# TOP.net
KiCad netlist of a schematic drawn in Altium Designer
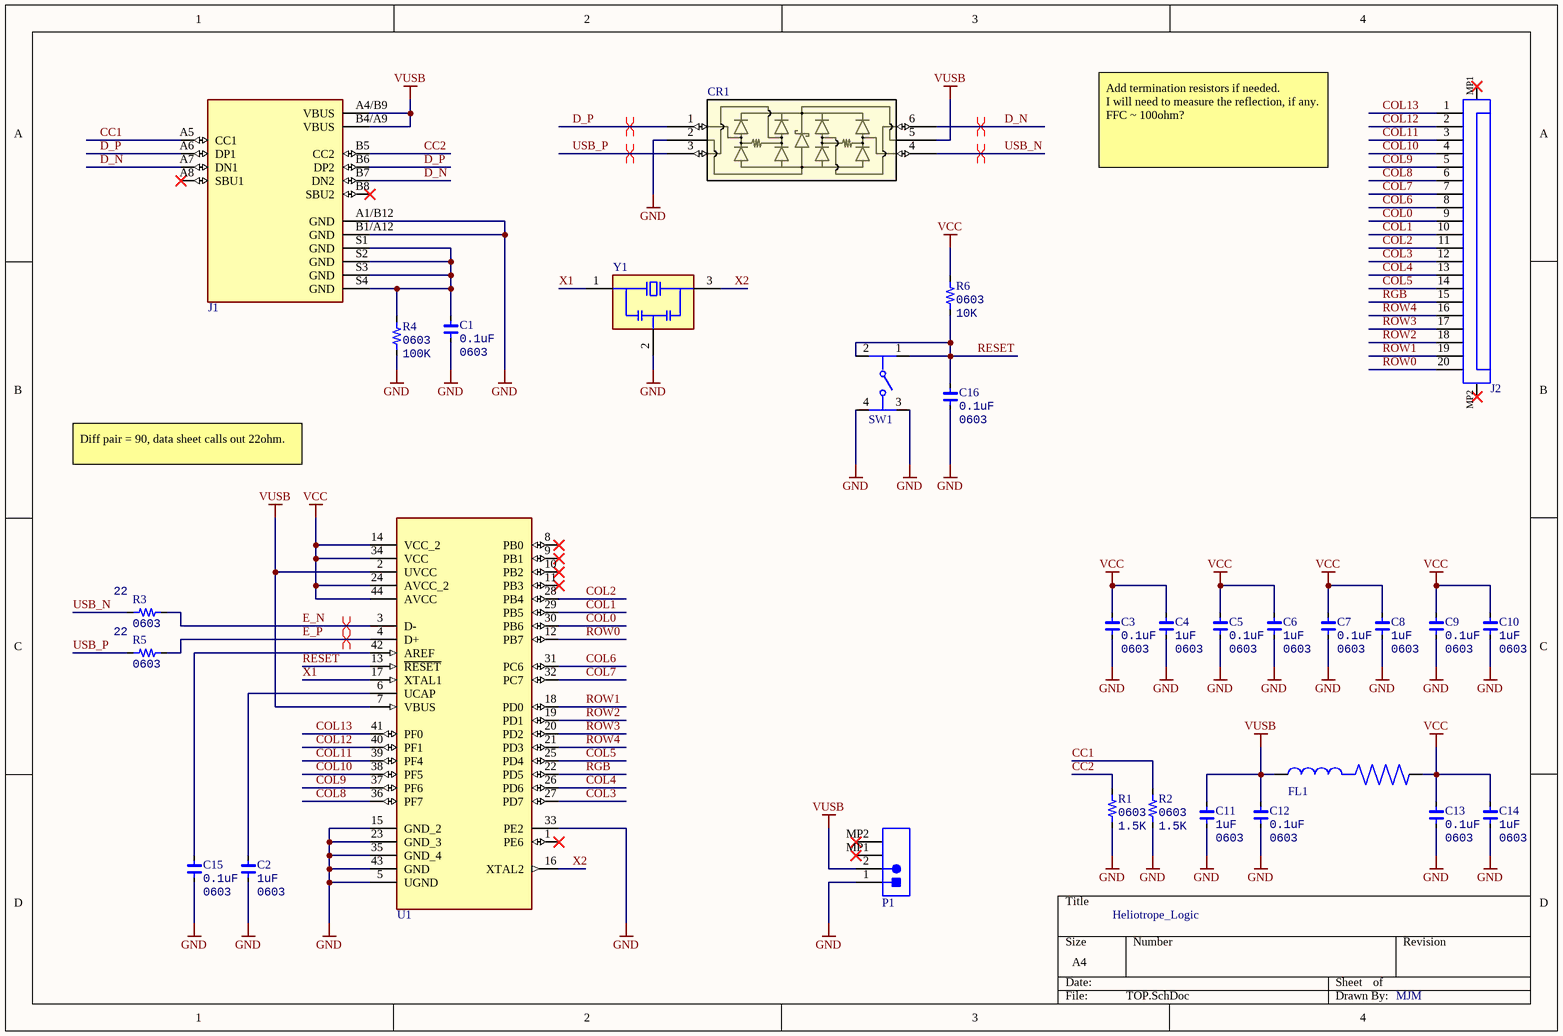
[diagram p0: TOP.SchDoc]

(export (version "E")
  (design (tool "Eeschema 10.0.6"))
  (components
    (comp (ref "C1")
      (value "0.1uF")
      (footprint "FP-CC0603-DA-MFG")
      (description "0603 0.1 uF 50 V ±5 % Tolerance X7R SMT Multilayer Ceramic Capacitor")
      (fields (field (name "TYPE") "0603") (field (name "Comment") "CC0603JRX7R9BB104"))
      (libsource (lib "Microcom Corporation") (part "M_Cap"))
    )
    (comp (ref "C2")
      (value "1uF")
      (footprint "FP-CC0603-DA-MFG")
      (description "Cap Ceramic 1uF 16V X7R 5% SMD 0603 125°C Paper T/R")
      (fields (field (name "TYPE") "0603") (field (name "Comment") "CC0603JRX7R7BB105"))
      (libsource (lib "Microcom Corporation") (part "M_Cap"))
    )
    (comp (ref "C3")
      (value "0.1uF")
      (footprint "FP-CC0603-DA-MFG")
      (description "0603 0.1 uF 50 V ±5 % Tolerance X7R SMT Multilayer Ceramic Capacitor")
      (fields (field (name "TYPE") "0603") (field (name "Comment") "CC0603JRX7R9BB104"))
      (libsource (lib "Microcom Corporation") (part "M_Cap"))
    )
    (comp (ref "C4")
      (value "1uF")
      (footprint "FP-CC0603-DA-MFG")
      (description "Cap Ceramic 1uF 16V X7R 5% SMD 0603 125°C Paper T/R")
      (fields (field (name "TYPE") "0603") (field (name "Comment") "CC0603JRX7R7BB105"))
      (libsource (lib "Microcom Corporation") (part "M_Cap"))
    )
    (comp (ref "C5")
      (value "0.1uF")
      (footprint "FP-CC0603-DA-MFG")
      (description "0603 0.1 uF 50 V ±5 % Tolerance X7R SMT Multilayer Ceramic Capacitor")
      (fields (field (name "TYPE") "0603") (field (name "Comment") "CC0603JRX7R9BB104"))
      (libsource (lib "Microcom Corporation") (part "M_Cap"))
    )
    (comp (ref "C6")
      (value "1uF")
      (footprint "FP-CC0603-DA-MFG")
      (description "Cap Ceramic 1uF 16V X7R 5% SMD 0603 125°C Paper T/R")
      (fields (field (name "TYPE") "0603") (field (name "Comment") "CC0603JRX7R7BB105"))
      (libsource (lib "Microcom Corporation") (part "M_Cap"))
    )
    (comp (ref "C7")
      (value "0.1uF")
      (footprint "FP-CC0603-DA-MFG")
      (description "0603 0.1 uF 50 V ±5 % Tolerance X7R SMT Multilayer Ceramic Capacitor")
      (fields (field (name "TYPE") "0603") (field (name "Comment") "CC0603JRX7R9BB104"))
      (libsource (lib "Microcom Corporation") (part "M_Cap"))
    )
    (comp (ref "C8")
      (value "1uF")
      (footprint "FP-CC0603-DA-MFG")
      (description "Cap Ceramic 1uF 16V X7R 5% SMD 0603 125°C Paper T/R")
      (fields (field (name "TYPE") "0603") (field (name "Comment") "CC0603JRX7R7BB105"))
      (libsource (lib "Microcom Corporation") (part "M_Cap"))
    )
    (comp (ref "C9")
      (value "0.1uF")
      (footprint "FP-CC0603-DA-MFG")
      (description "0603 0.1 uF 50 V ±5 % Tolerance X7R SMT Multilayer Ceramic Capacitor")
      (fields (field (name "TYPE") "0603") (field (name "Comment") "CC0603JRX7R9BB104"))
      (libsource (lib "Microcom Corporation") (part "M_Cap"))
    )
    (comp (ref "C10")
      (value "1uF")
      (footprint "FP-CC0603-DA-MFG")
      (description "Cap Ceramic 1uF 16V X7R 5% SMD 0603 125°C Paper T/R")
      (fields (field (name "TYPE") "0603") (field (name "Comment") "CC0603JRX7R7BB105"))
      (libsource (lib "Microcom Corporation") (part "M_Cap"))
    )
    (comp (ref "C11")
      (value "1uF")
      (footprint "FP-CC0603-DA-MFG")
      (description "Cap Ceramic 1uF 16V X7R 5% SMD 0603 125°C Paper T/R")
      (fields (field (name "TYPE") "0603") (field (name "Comment") "CC0603JRX7R7BB105"))
      (libsource (lib "Microcom Corporation") (part "M_Cap"))
    )
    (comp (ref "C12")
      (value "0.1uF")
      (footprint "FP-CC0603-DA-MFG")
      (description "0603 0.1 uF 50 V ±5 % Tolerance X7R SMT Multilayer Ceramic Capacitor")
      (fields (field (name "TYPE") "0603") (field (name "Comment") "CC0603JRX7R9BB104"))
      (libsource (lib "Microcom Corporation") (part "M_Cap"))
    )
    (comp (ref "C13")
      (value "0.1uF")
      (footprint "FP-CC0603-DA-MFG")
      (description "0603 0.1 uF 50 V ±5 % Tolerance X7R SMT Multilayer Ceramic Capacitor")
      (fields (field (name "TYPE") "0603") (field (name "Comment") "CC0603JRX7R9BB104"))
      (libsource (lib "Microcom Corporation") (part "M_Cap"))
    )
    (comp (ref "C14")
      (value "1uF")
      (footprint "FP-CC0603-DA-MFG")
      (description "Cap Ceramic 1uF 16V X7R 5% SMD 0603 125°C Paper T/R")
      (fields (field (name "TYPE") "0603") (field (name "Comment") "CC0603JRX7R7BB105"))
      (libsource (lib "Microcom Corporation") (part "M_Cap"))
    )
    (comp (ref "C15")
      (value "0.1uF")
      (footprint "FP-CC0603-DA-MFG")
      (description "0603 0.1 uF 50 V ±5 % Tolerance X7R SMT Multilayer Ceramic Capacitor")
      (fields (field (name "TYPE") "0603") (field (name "Comment") "CC0603JRX7R9BB104"))
      (libsource (lib "Microcom Corporation") (part "M_Cap"))
    )
    (comp (ref "C16")
      (value "0.1uF")
      (footprint "FP-CC0603-DA-MFG")
      (description "0603 0.1 uF 50 V ±5 % Tolerance X7R SMT Multilayer Ceramic Capacitor")
      (fields (field (name "TYPE") "0603") (field (name "Comment") "CC0603JRX7R9BB104"))
      (libsource (lib "Microcom Corporation") (part "M_Cap"))
    )
    (comp (ref "CR1")
      (value "IP4234CZ6,125")
      (footprint "TSOP6_SOT457_NEX")
      (description "TVS DIODE 5.5VWM 6TSOP")
      (libsource (lib "Microcom Corporation") (part "IP4234CZ6,125"))
    )
    (comp (ref "FL1")
      (value "BLM18AG601SN1D")
      (footprint "BEADC1608X95N")
      (description "600 Ohms @ 100MHz 1 Ferrite Bead 0603 _1608 Metric_ 500mA 380mOhm")
      (fields (field (name "DIGI-KEY_PART_NUMBER") "490-1014-1-ND") (field (name "MANUFACTURER") "Murata"))
      (libsource (lib "Microcom Corporation") (part "BLM18AG601SN1D"))
    )
    (comp (ref "J1")
      (value "USB4110-GF-A")
      (footprint "GCT_USB4110-GF-A_REVB")
      (description "Conn USB Type C RCP 16 POS 0.3mm/0.5mm Solder ST SMD 16 Terminal 1 Port T/R")
      (libsource (lib "Microcom Corporation") (part "USB4110-GF-A_REVB"))
    )
    (comp (ref "J2")
      (value "68712014522")
      (footprint "68712014522")
      (description "Ffc / Fpc Board Connector, Zif, Surface Mount, Plug, 20, Bottom, 0.5 Mm Rohs Compliant: Yes")
      (fields (field (name "MF") "Wurth Electronics"))
      (libsource (lib "Microcom Corporation") (part "WE-68X1201XXX22-20"))
    )
    (comp (ref "P1")
      (value "53261-0271")
      (footprint "MOLX-53261-0271_V")
      (description "1.25mm Pitch PicoBlade™ Header, Surface Mount, Right Angle, Lead-Free, 2 Circuits")
      (libsource (lib "Microcom Corporation") (part "CN-1P-2M-R2"))
    )
    (comp (ref "R1")
      (value "1.5K")
      (footprint "FP-RMCF0603-MFG")
      (description "Res Thick Film 0603 5.1K Ohm 5% 1/10W ±200ppm/°C Molded SMD Paper T/R")
      (fields (field (name "TYPE") "0603") (field (name "Comment") "RMCF0603JT5K10"))
      (libsource (lib "Microcom Corporation") (part "M_Res"))
    )
    (comp (ref "R2")
      (value "1.5K")
      (footprint "FP-RMCF0603-MFG")
      (description "Res Thick Film 0603 5.1K Ohm 5% 1/10W ±200ppm/°C Molded SMD Paper T/R")
      (fields (field (name "TYPE") "0603") (field (name "Comment") "RMCF0603JT5K10"))
      (libsource (lib "Microcom Corporation") (part "M_Res"))
    )
    (comp (ref "R3")
      (value "22")
      (footprint "FP-RMCF0603-MFG")
      (description "Res Thick Film 0603 22 Ohm 5% 1/10W ±200ppm/°C Molded SMD Paper T/R")
      (fields (field (name "TYPE") "0603") (field (name "Comment") "RMCF0603JT22R0"))
      (libsource (lib "Microcom Corporation") (part "M_Res"))
    )
    (comp (ref "R4")
      (value "100K")
      (footprint "FP-RMCF0603-MFG")
      (description "Res Thick Film 0603 100K Ohm 5% 1/10W ±200ppm/°C Molded SMD Paper T/R")
      (fields (field (name "TYPE") "0603") (field (name "Comment") "RMCF0603JT100K"))
      (libsource (lib "Microcom Corporation") (part "M_Res"))
    )
    (comp (ref "R5")
      (value "22")
      (footprint "FP-RMCF0603-MFG")
      (description "Res Thick Film 0603 22 Ohm 5% 1/10W ±200ppm/°C Molded SMD Paper T/R")
      (fields (field (name "TYPE") "0603") (field (name "Comment") "RMCF0603JT22R0"))
      (libsource (lib "Microcom Corporation") (part "M_Res"))
    )
    (comp (ref "R6")
      (value "10K")
      (footprint "FP-RMCF0603-MFG")
      (description "Res Thick Film 0603 10K Ohm 5% 1/10W ±100ppm/°C Molded SMD SMD Paper T/R")
      (fields (field (name "TYPE") "0603") (field (name "Comment") "RMCF0603JT10K0"))
      (libsource (lib "Microcom Corporation") (part "M_Res"))
    )
    (comp (ref "SW1")
      (value "PTS526SK15SMTR2LFS")
      (footprint "FP-PTS526SK15SMTR2LFS-MFG")
      (description "Switch Tactile N.O. SPST Round Button Gull Wing 0.05A 12VDC 200000Cycles 2.55N SMD T/R")
      (libsource (lib "Microcom Corporation") (part "b8895f3f4cefb76e1819d2863dba89b"))
    )
    (comp (ref "U1")
      (value "ATMEGA32U4-AU")
      (footprint "QFP80P1200X1200X120-44N")
      (description "IC MCU 8BIT 32KB FLASH 44TQFP")
      (fields (field (name "MF") "Microchip Technology / Atmel"))
      (libsource (lib "Microcom Corporation") (part "ATMEGA32U4-16AU"))
    )
    (comp (ref "Y1")
      (value "CSTNE16M0V51Z000R0")
      (footprint "OSC_CSTNE16M0V51Z000R0")
      (description "Ceramic Resonator 16MHz 5pF 3-Pin Surface Mount Emboss T/R")
      (fields (field (name "MF") "Murata Electronics"))
      (libsource (lib "Microcom Corporation") (part "CSTNE16M0V51Z000R0"))
    )
  )
  (nets
    (net (code "1") (name "/CC1") (class "Default")
      (node (ref "J1") (pin "A5") (pinfunction "CC1_A5") (pintype "bidirectional"))
      (node (ref "R2") (pin "2") (pinfunction "2_2") (pintype "passive"))
    )
    (net (code "2") (name "/CC2") (class "Default")
      (node (ref "J1") (pin "B5") (pinfunction "CC2_B5") (pintype "bidirectional"))
      (node (ref "R1") (pin "2") (pinfunction "2_2") (pintype "passive"))
    )
    (net (code "3") (name "/COL0") (class "Default")
      (node (ref "J2") (pin "9") (pinfunction "9_9") (pintype "passive"))
      (node (ref "U1") (pin "30") (pinfunction "PB6_30") (pintype "bidirectional"))
    )
    (net (code "4") (name "/COL1") (class "Default")
      (node (ref "J2") (pin "10") (pinfunction "10_10") (pintype "passive"))
      (node (ref "U1") (pin "29") (pinfunction "PB5_29") (pintype "bidirectional"))
    )
    (net (code "5") (name "/COL2") (class "Default")
      (node (ref "J2") (pin "11") (pinfunction "11_11") (pintype "passive"))
      (node (ref "U1") (pin "28") (pinfunction "PB4_28") (pintype "bidirectional"))
    )
    (net (code "6") (name "/COL3") (class "Default")
      (node (ref "J2") (pin "12") (pinfunction "12_12") (pintype "passive"))
      (node (ref "U1") (pin "27") (pinfunction "PD7_27") (pintype "bidirectional"))
    )
    (net (code "7") (name "/COL4") (class "Default")
      (node (ref "J2") (pin "13") (pinfunction "13_13") (pintype "passive"))
      (node (ref "U1") (pin "26") (pinfunction "PD6_26") (pintype "bidirectional"))
    )
    (net (code "8") (name "/COL5") (class "Default")
      (node (ref "J2") (pin "14") (pinfunction "14_14") (pintype "passive"))
      (node (ref "U1") (pin "25") (pinfunction "PD4_25") (pintype "bidirectional"))
    )
    (net (code "9") (name "/COL6") (class "Default")
      (node (ref "J2") (pin "8") (pinfunction "8_8") (pintype "passive"))
      (node (ref "U1") (pin "31") (pinfunction "PC6_31") (pintype "bidirectional"))
    )
    (net (code "10") (name "/COL7") (class "Default")
      (node (ref "J2") (pin "7") (pinfunction "7_7") (pintype "passive"))
      (node (ref "U1") (pin "32") (pinfunction "PC7_32") (pintype "bidirectional"))
    )
    (net (code "11") (name "/COL8") (class "Default")
      (node (ref "J2") (pin "6") (pinfunction "6_6") (pintype "passive"))
      (node (ref "U1") (pin "36") (pinfunction "PF7_36") (pintype "bidirectional"))
    )
    (net (code "12") (name "/COL9") (class "Default")
      (node (ref "J2") (pin "5") (pinfunction "5_5") (pintype "passive"))
      (node (ref "U1") (pin "37") (pinfunction "PF6_37") (pintype "bidirectional"))
    )
    (net (code "13") (name "/COL10") (class "Default")
      (node (ref "J2") (pin "4") (pinfunction "4_4") (pintype "passive"))
      (node (ref "U1") (pin "38") (pinfunction "PF5_38") (pintype "bidirectional"))
    )
    (net (code "14") (name "/COL11") (class "Default")
      (node (ref "J2") (pin "3") (pinfunction "3_3") (pintype "passive"))
      (node (ref "U1") (pin "39") (pinfunction "PF4_39") (pintype "bidirectional"))
    )
    (net (code "15") (name "/COL12") (class "Default")
      (node (ref "J2") (pin "2") (pinfunction "2_2") (pintype "passive"))
      (node (ref "U1") (pin "40") (pinfunction "PF1_40") (pintype "bidirectional"))
    )
    (net (code "16") (name "/COL13") (class "Default")
      (node (ref "J2") (pin "1") (pinfunction "1_1") (pintype "passive"))
      (node (ref "U1") (pin "41") (pinfunction "PF0_41") (pintype "bidirectional"))
    )
    (net (code "17") (name "/D_N") (class "Default")
      (node (ref "CR1") (pin "6") (pinfunction "ESD_PROTECTION_I/O_CHANNEL_2_6") (pintype "bidirectional"))
      (node (ref "J1") (pin "A7") (pinfunction "DN1_A7") (pintype "bidirectional"))
      (node (ref "J1") (pin "B7") (pinfunction "DN2_B7") (pintype "bidirectional"))
    )
    (net (code "18") (name "/D_P") (class "Default")
      (node (ref "CR1") (pin "1") (pinfunction "ESD_PROTECTION_I/O_CHANNEL_1_1") (pintype "bidirectional"))
      (node (ref "J1") (pin "A6") (pinfunction "DP1_A6") (pintype "bidirectional"))
      (node (ref "J1") (pin "B6") (pinfunction "DP2_B6") (pintype "bidirectional"))
    )
    (net (code "19") (name "/E_N") (class "Default")
      (node (ref "R3") (pin "2") (pinfunction "2_2") (pintype "passive"))
      (node (ref "U1") (pin "3") (pinfunction "D-_3") (pintype "passive"))
    )
    (net (code "20") (name "/E_P") (class "Default")
      (node (ref "R5") (pin "2") (pinfunction "2_2") (pintype "passive"))
      (node (ref "U1") (pin "4") (pinfunction "D+_4") (pintype "passive"))
    )
    (net (code "21") (name "/RESET") (class "Default")
      (node (ref "C16") (pin "2") (pinfunction "2_2") (pintype "passive"))
      (node (ref "R6") (pin "1") (pinfunction "1_1") (pintype "passive"))
      (node (ref "SW1") (pin "1") (pinfunction "1_1") (pintype "passive"))
      (node (ref "SW1") (pin "2") (pinfunction "2_2") (pintype "passive"))
      (node (ref "U1") (pin "13") (pinfunction "~{RESET}_13") (pintype "input"))
    )
    (net (code "22") (name "/RGB") (class "Default")
      (node (ref "J2") (pin "15") (pinfunction "15_15") (pintype "passive"))
      (node (ref "U1") (pin "22") (pinfunction "PD5_22") (pintype "bidirectional"))
    )
    (net (code "23") (name "/ROW0") (class "Default")
      (node (ref "J2") (pin "20") (pinfunction "20_20") (pintype "passive"))
      (node (ref "U1") (pin "12") (pinfunction "PB7_12") (pintype "bidirectional"))
    )
    (net (code "24") (name "/ROW1") (class "Default")
      (node (ref "J2") (pin "19") (pinfunction "19_19") (pintype "passive"))
      (node (ref "U1") (pin "18") (pinfunction "PD0_18") (pintype "bidirectional"))
    )
    (net (code "25") (name "/ROW2") (class "Default")
      (node (ref "J2") (pin "18") (pinfunction "18_18") (pintype "passive"))
      (node (ref "U1") (pin "19") (pinfunction "PD1_19") (pintype "bidirectional"))
    )
    (net (code "26") (name "/ROW3") (class "Default")
      (node (ref "J2") (pin "17") (pinfunction "17_17") (pintype "passive"))
      (node (ref "U1") (pin "20") (pinfunction "PD2_20") (pintype "bidirectional"))
    )
    (net (code "27") (name "/ROW4") (class "Default")
      (node (ref "J2") (pin "16") (pinfunction "16_16") (pintype "passive"))
      (node (ref "U1") (pin "21") (pinfunction "PD3_21") (pintype "bidirectional"))
    )
    (net (code "28") (name "/USB_N") (class "Default")
      (node (ref "CR1") (pin "4") (pinfunction "ESD_PROTECTION_I/O_CHANNEL_2_4") (pintype "bidirectional"))
      (node (ref "R3") (pin "1") (pinfunction "1_1") (pintype "passive"))
    )
    (net (code "29") (name "/USB_P") (class "Default")
      (node (ref "CR1") (pin "3") (pinfunction "ESD_PROTECTION_I/O_CHANNEL_1_3") (pintype "bidirectional"))
      (node (ref "R5") (pin "1") (pinfunction "1_1") (pintype "passive"))
    )
    (net (code "30") (name "/X1") (class "Default")
      (node (ref "U1") (pin "17") (pinfunction "XTAL1_17") (pintype "input"))
      (node (ref "Y1") (pin "1") (pinfunction "IN_1") (pintype "passive"))
    )
    (net (code "31") (name "/X2") (class "Default")
      (node (ref "U1") (pin "16") (pinfunction "XTAL2_16") (pintype "output"))
      (node (ref "Y1") (pin "3") (pinfunction "OUT_3") (pintype "passive"))
    )
    (net (code "32") (name "GND") (class "Default")
      (node (ref "C1") (pin "1") (pinfunction "1_1") (pintype "passive"))
      (node (ref "C10") (pin "1") (pinfunction "1_1") (pintype "passive"))
      (node (ref "C11") (pin "1") (pinfunction "1_1") (pintype "passive"))
      (node (ref "C12") (pin "1") (pinfunction "1_1") (pintype "passive"))
      (node (ref "C13") (pin "1") (pinfunction "1_1") (pintype "passive"))
      (node (ref "C14") (pin "1") (pinfunction "1_1") (pintype "passive"))
      (node (ref "C15") (pin "1") (pinfunction "1_1") (pintype "passive"))
      (node (ref "C16") (pin "1") (pinfunction "1_1") (pintype "passive"))
      (node (ref "C2") (pin "1") (pinfunction "1_1") (pintype "passive"))
      (node (ref "C3") (pin "1") (pinfunction "1_1") (pintype "passive"))
      (node (ref "C4") (pin "1") (pinfunction "1_1") (pintype "passive"))
      (node (ref "C5") (pin "1") (pinfunction "1_1") (pintype "passive"))
      (node (ref "C6") (pin "1") (pinfunction "1_1") (pintype "passive"))
      (node (ref "C7") (pin "1") (pinfunction "1_1") (pintype "passive"))
      (node (ref "C8") (pin "1") (pinfunction "1_1") (pintype "passive"))
      (node (ref "C9") (pin "1") (pinfunction "1_1") (pintype "passive"))
      (node (ref "CR1") (pin "2") (pinfunction "GROUND_2") (pintype "passive"))
      (node (ref "J1") (pin "A1/B12") (pinfunction "GND_A1/B12") (pintype "power_in"))
      (node (ref "J1") (pin "B1/A12") (pinfunction "GND_B1/A12") (pintype "power_in"))
      (node (ref "P1") (pin "1") (pinfunction "1_1") (pintype "passive"))
      (node (ref "R1") (pin "1") (pinfunction "1_1") (pintype "passive"))
      (node (ref "R2") (pin "1") (pinfunction "1_1") (pintype "passive"))
      (node (ref "R4") (pin "1") (pinfunction "1_1") (pintype "passive"))
      (node (ref "SW1") (pin "3") (pinfunction "3_3") (pintype "passive"))
      (node (ref "SW1") (pin "4") (pinfunction "4_4") (pintype "passive"))
      (node (ref "U1") (pin "15") (pinfunction "GND_2_15") (pintype "passive"))
      (node (ref "U1") (pin "23") (pinfunction "GND_3_23") (pintype "passive"))
      (node (ref "U1") (pin "33") (pinfunction "PE2_33") (pintype "passive"))
      (node (ref "U1") (pin "35") (pinfunction "GND_4_35") (pintype "passive"))
      (node (ref "U1") (pin "43") (pinfunction "GND_43") (pintype "passive"))
      (node (ref "U1") (pin "5") (pinfunction "UGND_5") (pintype "passive"))
      (node (ref "Y1") (pin "2") (pinfunction "GND_2") (pintype "power_in"))
    )
    (net (code "33") (name "Net-(C1-Pad2)") (class "Default")
      (node (ref "C1") (pin "2") (pinfunction "2_2") (pintype "passive"))
      (node (ref "J1") (pin "S1") (pinfunction "GND_S1") (pintype "power_in"))
      (node (ref "J1") (pin "S2") (pinfunction "GND_S2") (pintype "power_in"))
      (node (ref "J1") (pin "S3") (pinfunction "GND_S3") (pintype "power_in"))
      (node (ref "J1") (pin "S4") (pinfunction "GND_S4") (pintype "power_in"))
      (node (ref "R4") (pin "2") (pinfunction "2_2") (pintype "passive"))
    )
    (net (code "34") (name "Net-(U1-AREF)") (class "Default")
      (node (ref "C15") (pin "2") (pinfunction "2_2") (pintype "passive"))
      (node (ref "U1") (pin "42") (pinfunction "AREF_42") (pintype "input"))
    )
    (net (code "35") (name "Net-(U1-UCAP)") (class "Default")
      (node (ref "C2") (pin "2") (pinfunction "2_2") (pintype "passive"))
      (node (ref "U1") (pin "6") (pinfunction "UCAP_6") (pintype "power_in"))
    )
    (net (code "36") (name "VCC") (class "Default")
      (node (ref "C10") (pin "2") (pinfunction "2_2") (pintype "passive"))
      (node (ref "C13") (pin "2") (pinfunction "2_2") (pintype "passive"))
      (node (ref "C14") (pin "2") (pinfunction "2_2") (pintype "passive"))
      (node (ref "C3") (pin "2") (pinfunction "2_2") (pintype "passive"))
      (node (ref "C4") (pin "2") (pinfunction "2_2") (pintype "passive"))
      (node (ref "C5") (pin "2") (pinfunction "2_2") (pintype "passive"))
      (node (ref "C6") (pin "2") (pinfunction "2_2") (pintype "passive"))
      (node (ref "C7") (pin "2") (pinfunction "2_2") (pintype "passive"))
      (node (ref "C8") (pin "2") (pinfunction "2_2") (pintype "passive"))
      (node (ref "C9") (pin "2") (pinfunction "2_2") (pintype "passive"))
      (node (ref "FL1") (pin "2") (pinfunction "2_2") (pintype "passive"))
      (node (ref "R6") (pin "2") (pinfunction "2_2") (pintype "passive"))
      (node (ref "U1") (pin "14") (pinfunction "VCC_2_14") (pintype "power_in"))
      (node (ref "U1") (pin "24") (pinfunction "AVCC_2_24") (pintype "power_in"))
      (node (ref "U1") (pin "34") (pinfunction "VCC_34") (pintype "power_in"))
      (node (ref "U1") (pin "44") (pinfunction "AVCC_44") (pintype "power_in"))
    )
    (net (code "37") (name "VUSB") (class "Default")
      (node (ref "C11") (pin "2") (pinfunction "2_2") (pintype "passive"))
      (node (ref "C12") (pin "2") (pinfunction "2_2") (pintype "passive"))
      (node (ref "CR1") (pin "5") (pinfunction "SUPPLY_VOLTAGE_5") (pintype "power_in"))
      (node (ref "FL1") (pin "1") (pinfunction "1_1") (pintype "passive"))
      (node (ref "J1") (pin "A4/B9") (pinfunction "VBUS_A4/B9") (pintype "power_in"))
      (node (ref "J1") (pin "B4/A9") (pinfunction "VBUS_B4/A9") (pintype "power_in"))
      (node (ref "P1") (pin "2") (pinfunction "2_2") (pintype "passive"))
      (node (ref "U1") (pin "2") (pinfunction "UVCC_2") (pintype "power_in"))
      (node (ref "U1") (pin "7") (pinfunction "VBUS_7") (pintype "input"))
    )
    (net (code "38") (name "unconnected-(J1-SBU1-PadA8)") (class "Default")
      (node (ref "J1") (pin "A8") (pinfunction "SBU1_A8") (pintype "bidirectional+no_connect"))
    )
    (net (code "39") (name "unconnected-(J1-SBU2-PadB8)") (class "Default")
      (node (ref "J1") (pin "B8") (pinfunction "SBU2_B8") (pintype "bidirectional+no_connect"))
    )
    (net (code "40") (name "unconnected-(J2-PadMP1)") (class "Default")
      (node (ref "J2") (pin "MP1") (pinfunction "MP1_MP1") (pintype "passive+no_connect"))
    )
    (net (code "41") (name "unconnected-(J2-PadMP2)") (class "Default")
      (node (ref "J2") (pin "MP2") (pinfunction "MP2_MP2") (pintype "passive+no_connect"))
    )
    (net (code "42") (name "unconnected-(P1-PadMP1)") (class "Default")
      (node (ref "P1") (pin "MP1") (pinfunction "MP1_MP1") (pintype "passive+no_connect"))
    )
    (net (code "43") (name "unconnected-(P1-PadMP2)") (class "Default")
      (node (ref "P1") (pin "MP2") (pinfunction "MP2_MP2") (pintype "passive+no_connect"))
    )
    (net (code "44") (name "unconnected-(U1-PB0-Pad8)") (class "Default")
      (node (ref "U1") (pin "8") (pinfunction "PB0_8") (pintype "bidirectional+no_connect"))
    )
    (net (code "45") (name "unconnected-(U1-PB1-Pad9)") (class "Default")
      (node (ref "U1") (pin "9") (pinfunction "PB1_9") (pintype "bidirectional+no_connect"))
    )
    (net (code "46") (name "unconnected-(U1-PB2-Pad10)") (class "Default")
      (node (ref "U1") (pin "10") (pinfunction "PB2_10") (pintype "bidirectional+no_connect"))
    )
    (net (code "47") (name "unconnected-(U1-PB3-Pad11)") (class "Default")
      (node (ref "U1") (pin "11") (pinfunction "PB3_11") (pintype "bidirectional+no_connect"))
    )
    (net (code "48") (name "unconnected-(U1-PE6-Pad1)") (class "Default")
      (node (ref "U1") (pin "1") (pinfunction "PE6_1") (pintype "bidirectional+no_connect"))
    )
  )
)
